# Deneigus_POWER.net
KiCad netlist of a schematic drawn in Altium Designer
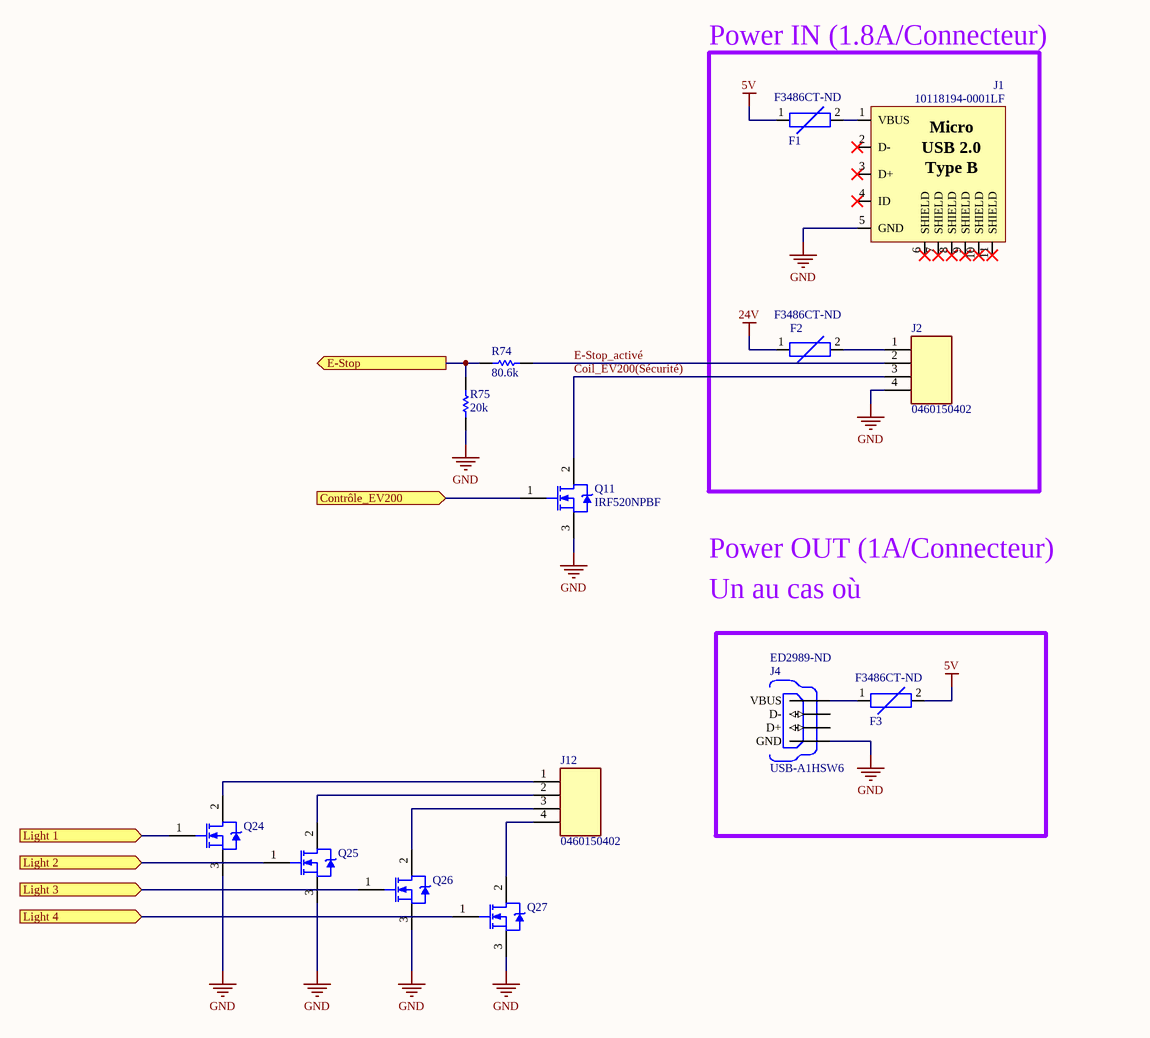
[diagram p0: Deneigus_POWER.SchDoc]

(export (version "E")
  (design (tool "Eeschema 10.0.6"))
  (components
    (comp (ref "F1")
      (value "0ZCG0075BF2B")
      (footprint "1812 (4532 Metric)")
      (fields (field (name "SUPPLIER PART NUMBER 1") "F3486CT-ND"))
      (libsource (lib "S7CAS-APP1") (part "PTC 33V 750 mA"))
    )
    (comp (ref "F2")
      (value "0ZCG0075BF2B")
      (footprint "1812 (4532 Metric)")
      (fields (field (name "SUPPLIER PART NUMBER 1") "F3486CT-ND"))
      (libsource (lib "S7CAS-APP1") (part "PTC 33V 750 mA"))
    )
    (comp (ref "F3")
      (value "0ZCG0075BF2B")
      (footprint "1812 (4532 Metric)")
      (fields (field (name "SUPPLIER PART NUMBER 1") "F3486CT-ND"))
      (libsource (lib "S7CAS-APP1") (part "PTC 33V 750 mA"))
    )
    (comp (ref "J1")
      (value "10118194-0001LF")
      (footprint "CON_USB_10118194-0001LF")
      (description "CON - USB MICRO B RECPT SMT R/A - 4PIN")
      (fields
        (field (name "CREATEDBY/DATE") "Arnaud Samson - 09/07/18")
        (field (name "VERIFIEDBY") "Jonathan Bouchard 2018-07-12")
      )
      (libsource (lib "S7CAS_LIB2021") (part "CON_USB_10118194-0001LF"))
    )
    (comp (ref "J2")
      (value "0460150402")
      (footprint "Molex_4PIN")
      (libsource (lib "S7CAS-APP1") (part "Molex_4PIN"))
    )
    (comp (ref "J4")
      (value "USB-A1HSW6")
      (footprint "USB-A1HSW6pcb:OST_USB-A1HSW6")
      (description "USB-A _USB TYPE-A_  Receptacle Connector 4 Position Through Hole, Right Angle")
      (fields (field (name "MF") "On Shore") (field (name "SUPPLIER PART NUMBER 1") "ED2989-ND"))
      (libsource (lib "USB-A1HSW6") (part "USB-A1HSW6"))
    )
    (comp (ref "J12")
      (value "0460150402")
      (footprint "Molex_4PIN")
      (libsource (lib "S7CAS-APP1") (part "Molex_4PIN"))
    )
    (comp (ref "Q11")
      (value "IRF520NPBF")
      (footprint "INTR-TO-220AB-3")
      (description "HEXFET(R) Power MOSFET, 100 V, 9.7 A, 0.2 Ohm, -55 to 175 degC, 3-Pin FM (TO-220AB), RoHS, Tube")
      (fields (field (name "POWER") "48W") (field (name "MANUFACTURER") "International Rectifier"))
      (libsource (lib "Université de Sherbrooke") (part "NEMOS-GDS-3_B"))
    )
    (comp (ref "Q24")
      (value "IRF520NPBF")
      (footprint "INTR-TO-220AB-3")
      (description "HEXFET(R) Power MOSFET, 100 V, 9.7 A, 0.2 Ohm, -55 to 175 degC, 3-Pin FM (TO-220AB), RoHS, Tube")
      (fields (field (name "POWER") "48W") (field (name "MANUFACTURER") "International Rectifier"))
      (libsource (lib "Université de Sherbrooke") (part "NEMOS-GDS-3_B"))
    )
    (comp (ref "Q25")
      (value "IRF520NPBF")
      (footprint "INTR-TO-220AB-3")
      (description "HEXFET(R) Power MOSFET, 100 V, 9.7 A, 0.2 Ohm, -55 to 175 degC, 3-Pin FM (TO-220AB), RoHS, Tube")
      (fields (field (name "POWER") "48W") (field (name "MANUFACTURER") "International Rectifier"))
      (libsource (lib "Université de Sherbrooke") (part "NEMOS-GDS-3_B"))
    )
    (comp (ref "Q26")
      (value "IRF520NPBF")
      (footprint "INTR-TO-220AB-3")
      (description "HEXFET(R) Power MOSFET, 100 V, 9.7 A, 0.2 Ohm, -55 to 175 degC, 3-Pin FM (TO-220AB), RoHS, Tube")
      (fields (field (name "POWER") "48W") (field (name "MANUFACTURER") "International Rectifier"))
      (libsource (lib "Université de Sherbrooke") (part "NEMOS-GDS-3_B"))
    )
    (comp (ref "Q27")
      (value "IRF520NPBF")
      (footprint "INTR-TO-220AB-3")
      (description "HEXFET(R) Power MOSFET, 100 V, 9.7 A, 0.2 Ohm, -55 to 175 degC, 3-Pin FM (TO-220AB), RoHS, Tube")
      (fields (field (name "POWER") "48W") (field (name "MANUFACTURER") "International Rectifier"))
      (libsource (lib "Université de Sherbrooke") (part "NEMOS-GDS-3_B"))
    )
    (comp (ref "R74")
      (value "80.6k")
      (footprint "RES_0805")
      (description "Resistor")
      (fields (field (name "Comment") "Res1") (field (name "PUBLISHER") "Altium Limited"))
      (libsource (lib "Miscellaneous Devices") (part "Res1"))
    )
    (comp (ref "R75")
      (value "20k")
      (footprint "RES_0805")
      (description "Resistor")
      (fields (field (name "Comment") "Res1") (field (name "PUBLISHER") "Altium Limited"))
      (libsource (lib "Miscellaneous Devices") (part "Res1"))
    )
  )
  (nets
    (net (code "1") (name "/Coil_EV200(Sécurité)") (class "Default")
      (node (ref "J2") (pin "3") (pinfunction "3_3") (pintype "passive"))
      (node (ref "Q11") (pin "2") (pinfunction "D_2") (pintype "passive"))
    )
    (net (code "2") (name "/Contrôle_EV200") (class "Default")
      (node (ref "Q11") (pin "1") (pinfunction "G_1") (pintype "passive"))
    )
    (net (code "3") (name "/E-Stop") (class "Default")
      (node (ref "R74") (pin "2") (pinfunction "2_2") (pintype "passive"))
      (node (ref "R75") (pin "1") (pinfunction "1_1") (pintype "passive"))
    )
    (net (code "4") (name "/E-Stop_activé") (class "Default")
      (node (ref "J2") (pin "2") (pinfunction "2_2") (pintype "passive"))
      (node (ref "R74") (pin "1") (pinfunction "1_1") (pintype "passive"))
    )
    (net (code "5") (name "/Light 1") (class "Default")
      (node (ref "Q24") (pin "1") (pinfunction "G_1") (pintype "passive"))
    )
    (net (code "6") (name "/Light 2") (class "Default")
      (node (ref "Q25") (pin "1") (pinfunction "G_1") (pintype "passive"))
    )
    (net (code "7") (name "/Light 3") (class "Default")
      (node (ref "Q26") (pin "1") (pinfunction "G_1") (pintype "passive"))
    )
    (net (code "8") (name "/Light 4") (class "Default")
      (node (ref "Q27") (pin "1") (pinfunction "G_1") (pintype "passive"))
    )
    (net (code "9") (name "5V") (class "Default")
      (node (ref "F1") (pin "1") (pinfunction "1_1") (pintype "passive"))
      (node (ref "F3") (pin "2") (pinfunction "2_2") (pintype "passive"))
    )
    (net (code "10") (name "24V") (class "Default")
      (node (ref "F2") (pin "1") (pinfunction "1_1") (pintype "passive"))
    )
    (net (code "11") (name "GND") (class "Default")
      (node (ref "J1") (pin "5") (pinfunction "GND_5") (pintype "passive"))
      (node (ref "J2") (pin "4") (pinfunction "4_4") (pintype "passive"))
      (node (ref "J4") (pin "4") (pinfunction "GND_4") (pintype "power_in"))
      (node (ref "Q11") (pin "3") (pinfunction "S_3") (pintype "passive"))
      (node (ref "Q24") (pin "3") (pinfunction "S_3") (pintype "passive"))
      (node (ref "Q25") (pin "3") (pinfunction "S_3") (pintype "passive"))
      (node (ref "Q26") (pin "3") (pinfunction "S_3") (pintype "passive"))
      (node (ref "Q27") (pin "3") (pinfunction "S_3") (pintype "passive"))
      (node (ref "R75") (pin "2") (pinfunction "2_2") (pintype "passive"))
    )
    (net (code "12") (name "Net-(F2-Pad2)") (class "Default")
      (node (ref "F2") (pin "2") (pinfunction "2_2") (pintype "passive"))
      (node (ref "J2") (pin "1") (pinfunction "1_1") (pintype "passive"))
    )
    (net (code "13") (name "Net-(J1-VBUS)") (class "Default")
      (node (ref "F1") (pin "2") (pinfunction "2_2") (pintype "passive"))
      (node (ref "J1") (pin "1") (pinfunction "VBUS_1") (pintype "passive"))
    )
    (net (code "14") (name "Net-(J4-VBUS)") (class "Default")
      (node (ref "F3") (pin "1") (pinfunction "1_1") (pintype "passive"))
      (node (ref "J4") (pin "1") (pinfunction "VBUS_1") (pintype "power_in"))
    )
    (net (code "15") (name "Net-(Q24-D)") (class "Default")
      (node (ref "J12") (pin "1") (pinfunction "1_1") (pintype "passive"))
      (node (ref "Q24") (pin "2") (pinfunction "D_2") (pintype "passive"))
    )
    (net (code "16") (name "Net-(Q25-D)") (class "Default")
      (node (ref "J12") (pin "2") (pinfunction "2_2") (pintype "passive"))
      (node (ref "Q25") (pin "2") (pinfunction "D_2") (pintype "passive"))
    )
    (net (code "17") (name "Net-(Q26-D)") (class "Default")
      (node (ref "J12") (pin "3") (pinfunction "3_3") (pintype "passive"))
      (node (ref "Q26") (pin "2") (pinfunction "D_2") (pintype "passive"))
    )
    (net (code "18") (name "Net-(Q27-D)") (class "Default")
      (node (ref "J12") (pin "4") (pinfunction "4_4") (pintype "passive"))
      (node (ref "Q27") (pin "2") (pinfunction "D_2") (pintype "passive"))
    )
    (net (code "19") (name "unconnected-(J1-D+-Pad3)") (class "Default")
      (node (ref "J1") (pin "3") (pinfunction "D+_3") (pintype "passive+no_connect"))
    )
    (net (code "20") (name "unconnected-(J1-D--Pad2)") (class "Default")
      (node (ref "J1") (pin "2") (pinfunction "D-_2") (pintype "passive+no_connect"))
    )
    (net (code "21") (name "unconnected-(J1-ID-Pad4)") (class "Default")
      (node (ref "J1") (pin "4") (pinfunction "ID_4") (pintype "passive+no_connect"))
    )
    (net (code "22") (name "unconnected-(J1-SHIELD-Pad6)") (class "Default")
      (node (ref "J1") (pin "6") (pinfunction "SHIELD_6") (pintype "passive+no_connect"))
    )
    (net (code "23") (name "unconnected-(J1-SHIELD-Pad7)") (class "Default")
      (node (ref "J1") (pin "7") (pinfunction "SHIELD_7") (pintype "passive+no_connect"))
    )
    (net (code "24") (name "unconnected-(J1-SHIELD-Pad8)") (class "Default")
      (node (ref "J1") (pin "8") (pinfunction "SHIELD_8") (pintype "passive+no_connect"))
    )
    (net (code "25") (name "unconnected-(J1-SHIELD-Pad9)") (class "Default")
      (node (ref "J1") (pin "9") (pinfunction "SHIELD_9") (pintype "passive+no_connect"))
    )
    (net (code "26") (name "unconnected-(J1-SHIELD-Pad10)") (class "Default")
      (node (ref "J1") (pin "10") (pinfunction "SHIELD_10") (pintype "passive+no_connect"))
    )
    (net (code "27") (name "unconnected-(J1-SHIELD-Pad11)") (class "Default")
      (node (ref "J1") (pin "11") (pinfunction "SHIELD_11") (pintype "passive+no_connect"))
    )
    (net (code "28") (name "unconnected-(J4-D+-Pad3)") (class "Default")
      (node (ref "J4") (pin "3") (pinfunction "D+_3") (pintype "bidirectional"))
    )
    (net (code "29") (name "unconnected-(J4-D--Pad2)") (class "Default")
      (node (ref "J4") (pin "2") (pinfunction "D-_2") (pintype "bidirectional"))
    )
  )
)
